# Nakuja_Remix_3.net
KiCad netlist of a schematic drawn in EasyEDA
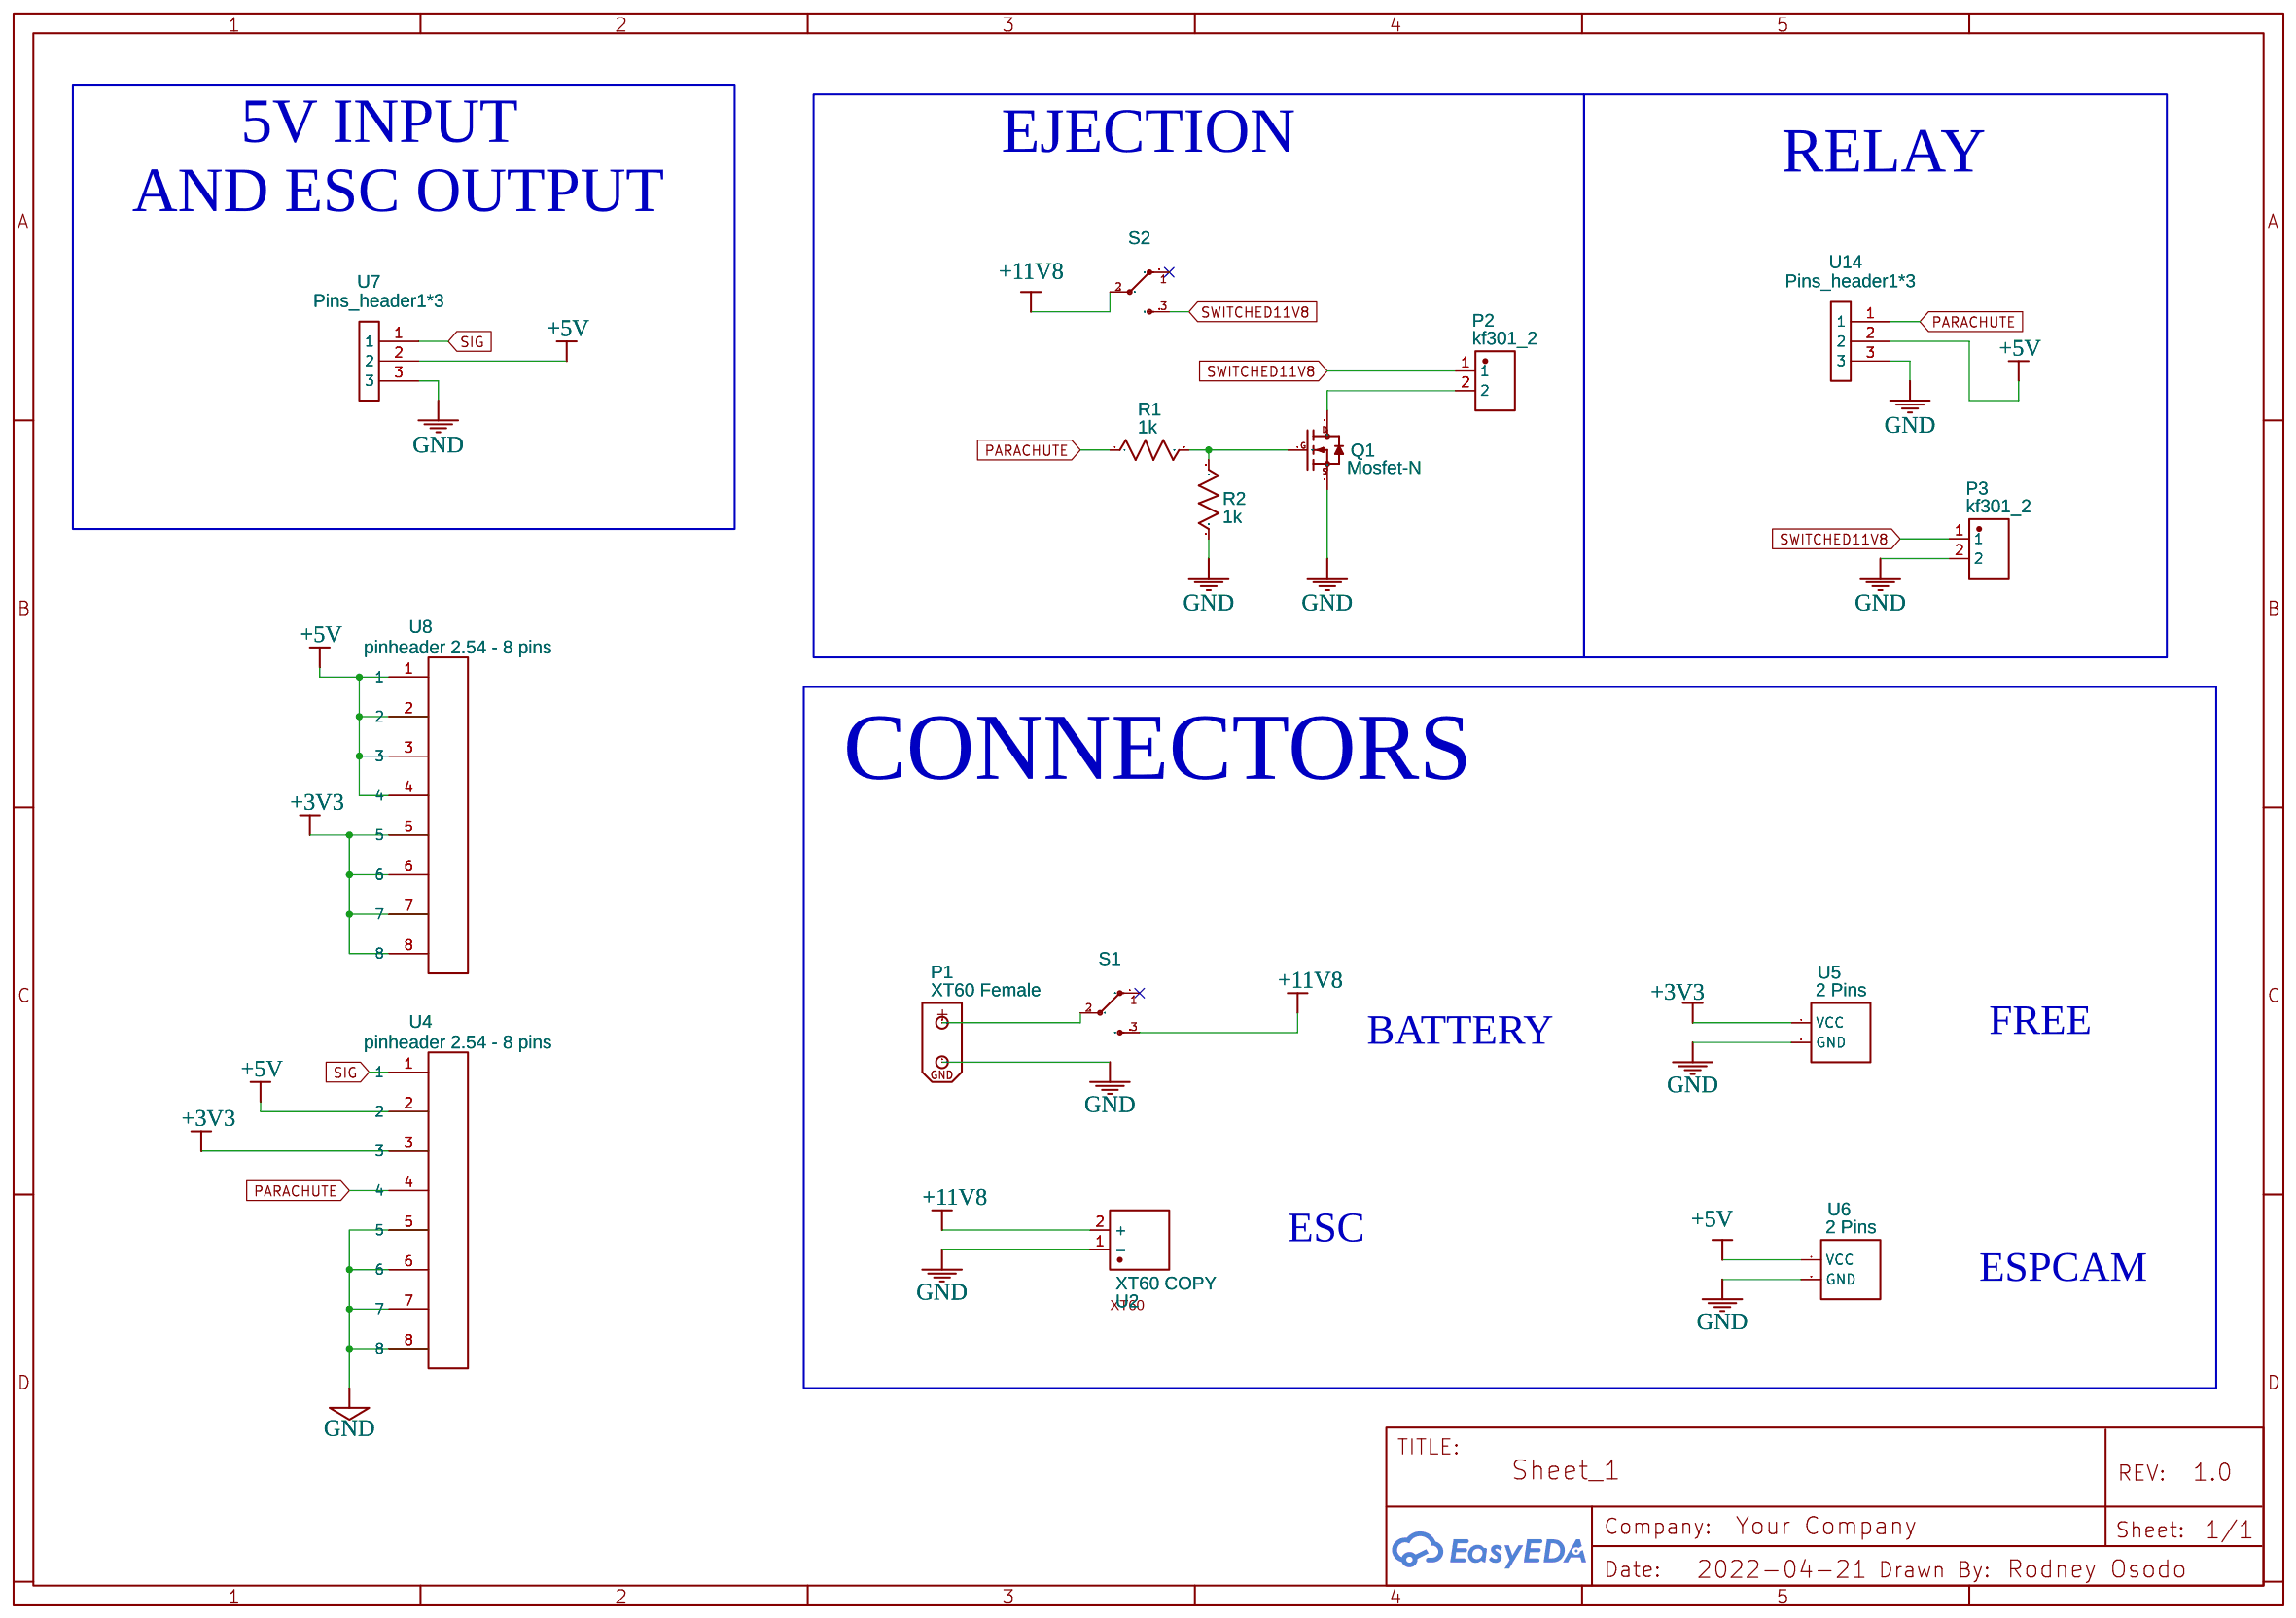
[diagram p0: schematic sheet]

(export (version "E")
  (design (tool "Eeschema 10.0.6"))
  (components
    (comp (ref "P1")
      (value "XT60 Female")
      (fields (field (name "BOM_Manufacturer Part") "XT60-F"))
      (libsource (lib "") (part "XT60 Female"))
    )
    (comp (ref "P2")
      (value "kf301_2")
      (fields (field (name "BOM_Supplier Part") "C33435"))
      (libsource (lib "") (part "kf301_2"))
    )
    (comp (ref "P3")
      (value "kf301_2")
      (fields (field (name "BOM_Supplier Part") "C33435"))
      (libsource (lib "") (part "kf301_2"))
    )
    (comp (ref "Q1") (value "Mosfet-N") (libsource (lib "") (part "Mosfet-N")))
    (comp (ref "R1") (value "1k") (libsource (lib "") (part "R_AXIAL-0.6_US")))
    (comp (ref "R2") (value "1k") (libsource (lib "") (part "R_AXIAL-0.6_US_1")))
    (comp (ref "S1")
      (value "TOGGLESWITCH SPST_SWITCH-SPDT")
      (libsource (lib "") (part "TOGGLESWITCH SPST_SWITCH-SPDT"))
    )
    (comp (ref "S2")
      (value "TOGGLESWITCH SPST_SWITCH-SPDT")
      (libsource (lib "") (part "TOGGLESWITCH SPST_SWITCH-SPDT"))
    )
    (comp (ref "U2") (value "XT60 COPY") (libsource (lib "") (part "XT60 COPY")))
    (comp (ref "U4") (value "pinheader 2.54 - 8 pins") (libsource (lib "") (part "pinheader 2.54 - 8 pins")))
    (comp (ref "U5") (value "2 Pins") (libsource (lib "") (part "2 Pins")))
    (comp (ref "U6") (value "2 Pins") (libsource (lib "") (part "2 Pins")))
    (comp (ref "U7") (value "Pins_header1*3") (libsource (lib "") (part "Pins_header1*3")))
    (comp (ref "U8") (value "pinheader 2.54 - 8 pins") (libsource (lib "") (part "pinheader 2.54 - 8 pins")))
    (comp (ref "U14") (value "Pins_header1*3") (libsource (lib "") (part "Pins_header1*3")))
  )
  (nets
    (net (code "1") (name "+3V3") (class "Default")
      (node (ref "U4") (pin "3") (pinfunction "3_3") (pintype "unspecified"))
      (node (ref "U5") (pin "1") (pinfunction "VCC_1") (pintype "unspecified"))
      (node (ref "U8") (pin "5") (pinfunction "5_5") (pintype "unspecified"))
      (node (ref "U8") (pin "6") (pinfunction "6_6") (pintype "unspecified"))
      (node (ref "U8") (pin "7") (pinfunction "7_7") (pintype "unspecified"))
      (node (ref "U8") (pin "8") (pinfunction "8_8") (pintype "unspecified"))
    )
    (net (code "2") (name "+5V") (class "Default")
      (node (ref "U14") (pin "2") (pinfunction "2_2") (pintype "unspecified"))
      (node (ref "U4") (pin "2") (pinfunction "2_2") (pintype "unspecified"))
      (node (ref "U6") (pin "1") (pinfunction "VCC_1") (pintype "unspecified"))
      (node (ref "U7") (pin "2") (pinfunction "2_2") (pintype "unspecified"))
      (node (ref "U8") (pin "1") (pinfunction "1_1") (pintype "unspecified"))
      (node (ref "U8") (pin "2") (pinfunction "2_2") (pintype "unspecified"))
      (node (ref "U8") (pin "3") (pinfunction "3_3") (pintype "unspecified"))
      (node (ref "U8") (pin "4") (pinfunction "4_4") (pintype "unspecified"))
    )
    (net (code "3") (name "+11V8") (class "Default")
      (node (ref "S1") (pin "3") (pinfunction "S_3") (pintype "unspecified"))
      (node (ref "S2") (pin "2") (pinfunction "P_2") (pintype "unspecified"))
      (node (ref "U2") (pin "2") (pinfunction "+_2") (pintype "unspecified"))
    )
    (net (code "4") (name "GND") (class "Default")
      (node (ref "P1") (pin "1") (pinfunction "1_1") (pintype "unspecified"))
      (node (ref "P3") (pin "2") (pinfunction "2_2") (pintype "unspecified"))
      (node (ref "Q1") (pin "3") (pinfunction "S_3") (pintype "unspecified"))
      (node (ref "R2") (pin "1") (pinfunction "1_1") (pintype "unspecified"))
      (node (ref "U14") (pin "3") (pinfunction "3_3") (pintype "unspecified"))
      (node (ref "U2") (pin "1") (pinfunction "-_1") (pintype "unspecified"))
      (node (ref "U4") (pin "5") (pinfunction "5_5") (pintype "unspecified"))
      (node (ref "U4") (pin "6") (pinfunction "6_6") (pintype "unspecified"))
      (node (ref "U4") (pin "7") (pinfunction "7_7") (pintype "unspecified"))
      (node (ref "U4") (pin "8") (pinfunction "8_8") (pintype "unspecified"))
      (node (ref "U5") (pin "2") (pinfunction "GND_2") (pintype "unspecified"))
      (node (ref "U6") (pin "2") (pinfunction "GND_2") (pintype "unspecified"))
      (node (ref "U7") (pin "3") (pinfunction "3_3") (pintype "unspecified"))
    )
    (net (code "5") (name "Net-(Q1-D)") (class "Default")
      (node (ref "P2") (pin "2") (pinfunction "2_2") (pintype "unspecified"))
      (node (ref "Q1") (pin "2") (pinfunction "D_2") (pintype "unspecified"))
    )
    (net (code "6") (name "Net-(Q1-G)") (class "Default")
      (node (ref "Q1") (pin "1") (pinfunction "G_1") (pintype "unspecified"))
      (node (ref "R1") (pin "2") (pinfunction "2_2") (pintype "unspecified"))
      (node (ref "R2") (pin "2") (pinfunction "2_2") (pintype "unspecified"))
    )
    (net (code "7") (name "Net-(S1-P)") (class "Default")
      (node (ref "P1") (pin "2") (pinfunction "2_2") (pintype "unspecified"))
      (node (ref "S1") (pin "2") (pinfunction "P_2") (pintype "unspecified"))
    )
    (net (code "8") (name "PARACHUTE") (class "Default")
      (node (ref "R1") (pin "1") (pinfunction "1_1") (pintype "unspecified"))
      (node (ref "U14") (pin "1") (pinfunction "1_1") (pintype "unspecified"))
      (node (ref "U4") (pin "4") (pinfunction "4_4") (pintype "unspecified"))
    )
    (net (code "9") (name "SIG") (class "Default")
      (node (ref "U4") (pin "1") (pinfunction "1_1") (pintype "unspecified"))
      (node (ref "U7") (pin "1") (pinfunction "1_1") (pintype "unspecified"))
    )
    (net (code "10") (name "SWITCHED11V8") (class "Default")
      (node (ref "P2") (pin "1") (pinfunction "1_1") (pintype "unspecified"))
      (node (ref "P3") (pin "1") (pinfunction "1_1") (pintype "unspecified"))
      (node (ref "S2") (pin "3") (pinfunction "S_3") (pintype "unspecified"))
    )
    (net (code "11") (name "unconnected-(S1-O-Pad1)") (class "Default")
      (node (ref "S1") (pin "1") (pinfunction "O_1") (pintype "unspecified+no_connect"))
    )
    (net (code "12") (name "unconnected-(S2-O-Pad1)") (class "Default")
      (node (ref "S2") (pin "1") (pinfunction "O_1") (pintype "unspecified+no_connect"))
    )
  )
)
